# EXT_LED.net
KiCad netlist of a schematic drawn in EAGLE
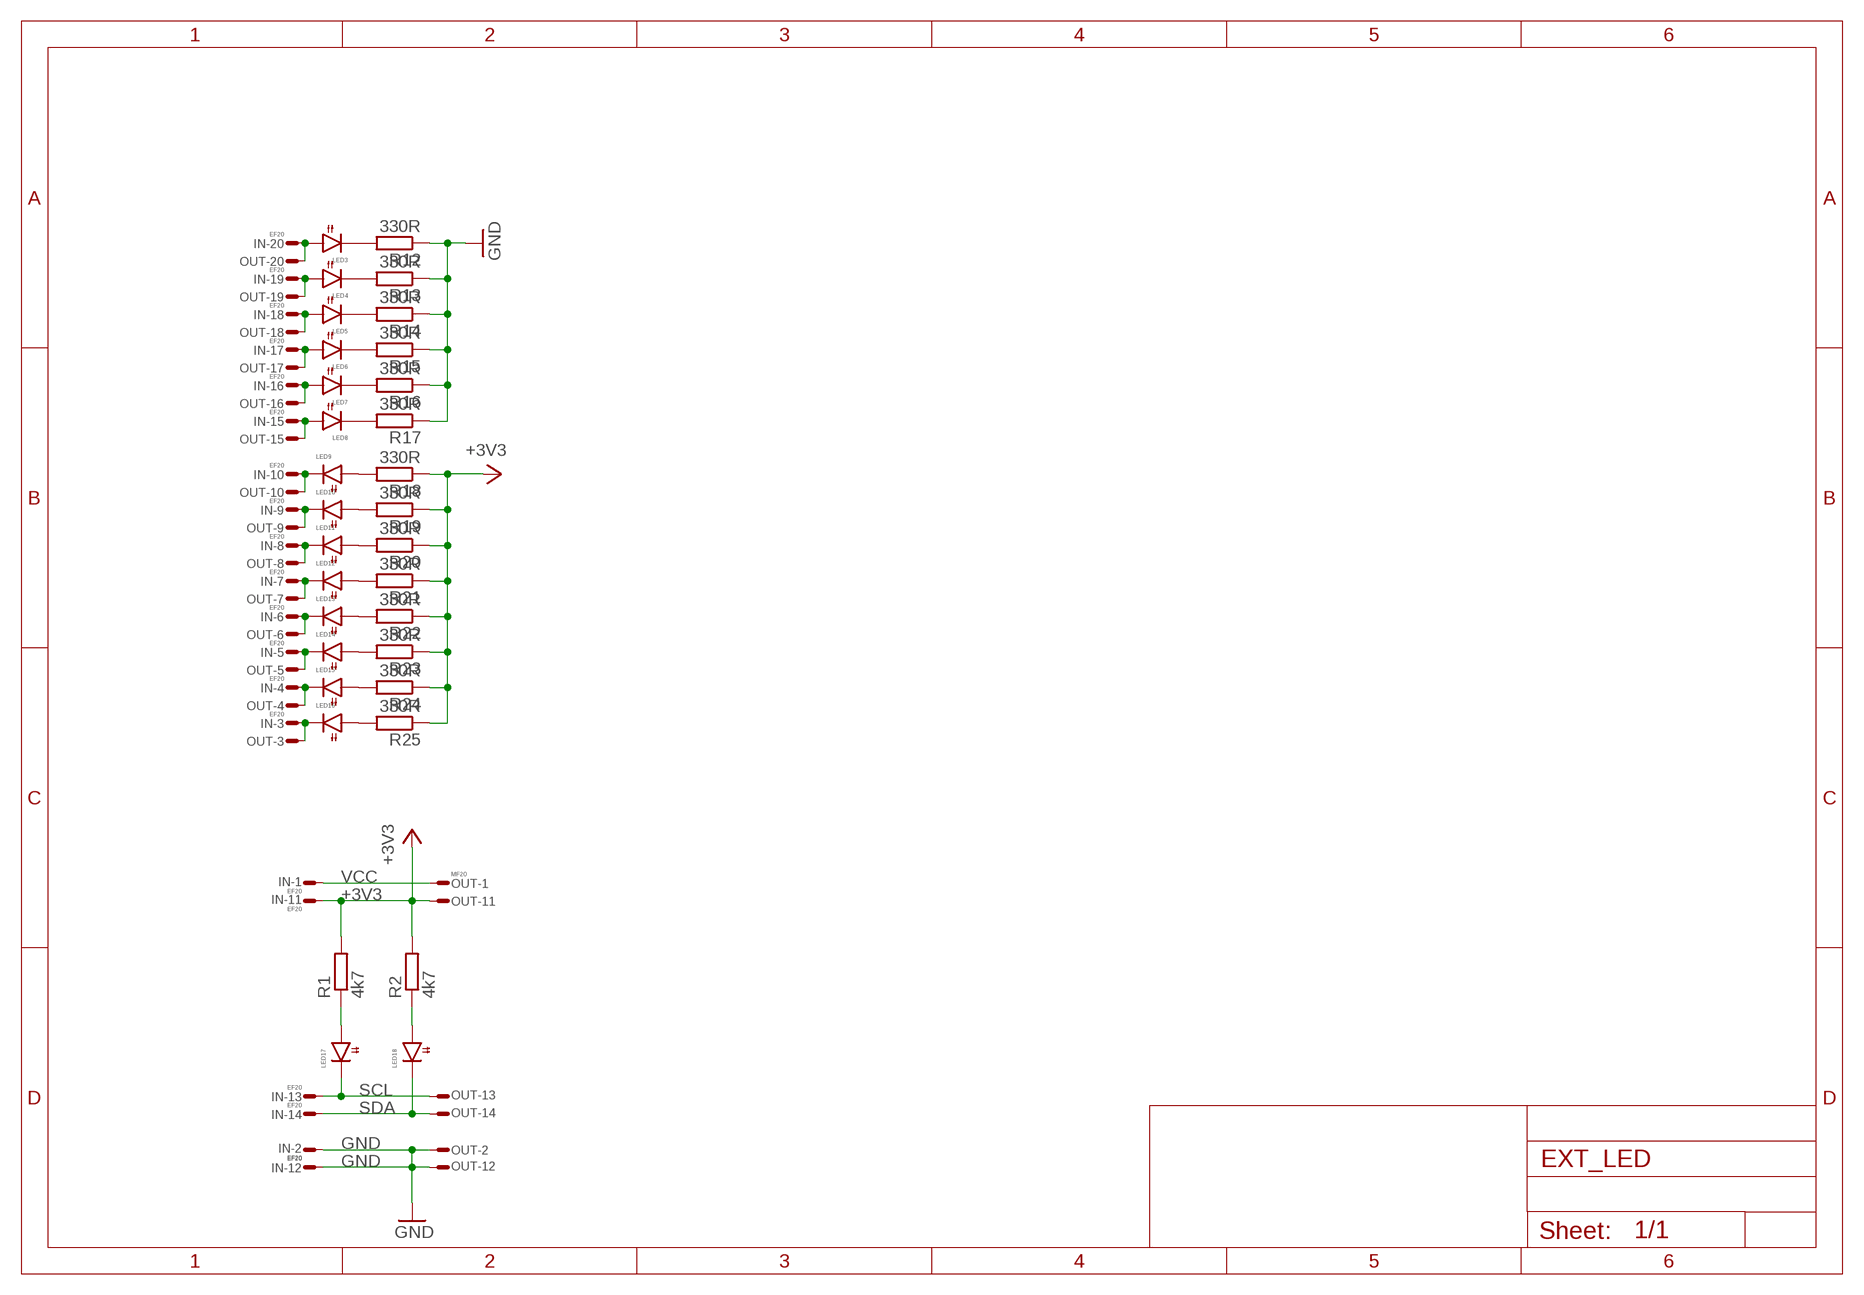
[diagram p0: schematic, sheet 1]

(export (version "E")
  (design (tool "Eeschema 10.0.6"))
  (components
    (comp (ref "IN")
      (value "EF20")
      (footprint "eagle-import:FE10-2WSS")
      (libsource (lib "eagle-import") (part "FE20ELSS"))
    )
    (comp (ref "LED3")
      (value "LED0603")
      (footprint "eagle-import:0603")
      (libsource (lib "eagle-import") (part "LED0603"))
    )
    (comp (ref "LED4")
      (value "LED0603")
      (footprint "eagle-import:0603")
      (libsource (lib "eagle-import") (part "LED0603"))
    )
    (comp (ref "LED5")
      (value "LED0603")
      (footprint "eagle-import:0603")
      (libsource (lib "eagle-import") (part "LED0603"))
    )
    (comp (ref "LED6")
      (value "LED0603")
      (footprint "eagle-import:0603")
      (libsource (lib "eagle-import") (part "LED0603"))
    )
    (comp (ref "LED7")
      (value "LED0603")
      (footprint "eagle-import:0603")
      (libsource (lib "eagle-import") (part "LED0603"))
    )
    (comp (ref "LED8")
      (value "LED0603")
      (footprint "eagle-import:0603")
      (libsource (lib "eagle-import") (part "LED0603"))
    )
    (comp (ref "LED9")
      (value "LED0603")
      (footprint "eagle-import:0603")
      (libsource (lib "eagle-import") (part "LED0603"))
    )
    (comp (ref "LED10")
      (value "LED0603")
      (footprint "eagle-import:0603")
      (libsource (lib "eagle-import") (part "LED0603"))
    )
    (comp (ref "LED11")
      (value "LED0603")
      (footprint "eagle-import:0603")
      (libsource (lib "eagle-import") (part "LED0603"))
    )
    (comp (ref "LED12")
      (value "LED0603")
      (footprint "eagle-import:0603")
      (libsource (lib "eagle-import") (part "LED0603"))
    )
    (comp (ref "LED13")
      (value "LED0603")
      (footprint "eagle-import:0603")
      (libsource (lib "eagle-import") (part "LED0603"))
    )
    (comp (ref "LED14")
      (value "LED0603")
      (footprint "eagle-import:0603")
      (libsource (lib "eagle-import") (part "LED0603"))
    )
    (comp (ref "LED15")
      (value "LED0603")
      (footprint "eagle-import:0603")
      (libsource (lib "eagle-import") (part "LED0603"))
    )
    (comp (ref "LED16")
      (value "LED0603")
      (footprint "eagle-import:0603")
      (libsource (lib "eagle-import") (part "LED0603"))
    )
    (comp (ref "LED17")
      (value "LED0603")
      (footprint "eagle-import:0603")
      (libsource (lib "eagle-import") (part "LED0603"))
    )
    (comp (ref "LED18")
      (value "LED0603")
      (footprint "eagle-import:0603")
      (libsource (lib "eagle-import") (part "LED0603"))
    )
    (comp (ref "OUT")
      (value "MF20")
      (footprint "eagle-import:ML20LS")
      (libsource (lib "eagle-import") (part "ML20?ELS"))
    )
    (comp (ref "R1")
      (value "4k7")
      (footprint "eagle-import:0603")
      (libsource (lib "eagle-import") (part "R0603"))
    )
    (comp (ref "R2")
      (value "4k7")
      (footprint "eagle-import:0603")
      (libsource (lib "eagle-import") (part "R0603"))
    )
    (comp (ref "R12")
      (value "330R")
      (footprint "eagle-import:0603")
      (libsource (lib "eagle-import") (part "R0603"))
    )
    (comp (ref "R13")
      (value "330R")
      (footprint "eagle-import:0603")
      (libsource (lib "eagle-import") (part "R0603"))
    )
    (comp (ref "R14")
      (value "330R")
      (footprint "eagle-import:0603")
      (libsource (lib "eagle-import") (part "R0603"))
    )
    (comp (ref "R15")
      (value "330R")
      (footprint "eagle-import:0603")
      (libsource (lib "eagle-import") (part "R0603"))
    )
    (comp (ref "R16")
      (value "330R")
      (footprint "eagle-import:0603")
      (libsource (lib "eagle-import") (part "R0603"))
    )
    (comp (ref "R17")
      (value "330R")
      (footprint "eagle-import:0603")
      (libsource (lib "eagle-import") (part "R0603"))
    )
    (comp (ref "R18")
      (value "330R")
      (footprint "eagle-import:0603")
      (libsource (lib "eagle-import") (part "R0603"))
    )
    (comp (ref "R19")
      (value "330R")
      (footprint "eagle-import:0603")
      (libsource (lib "eagle-import") (part "R0603"))
    )
    (comp (ref "R20")
      (value "330R")
      (footprint "eagle-import:0603")
      (libsource (lib "eagle-import") (part "R0603"))
    )
    (comp (ref "R21")
      (value "330R")
      (footprint "eagle-import:0603")
      (libsource (lib "eagle-import") (part "R0603"))
    )
    (comp (ref "R22")
      (value "330R")
      (footprint "eagle-import:0603")
      (libsource (lib "eagle-import") (part "R0603"))
    )
    (comp (ref "R23")
      (value "330R")
      (footprint "eagle-import:0603")
      (libsource (lib "eagle-import") (part "R0603"))
    )
    (comp (ref "R24")
      (value "330R")
      (footprint "eagle-import:0603")
      (libsource (lib "eagle-import") (part "R0603"))
    )
    (comp (ref "R25")
      (value "330R")
      (footprint "eagle-import:0603")
      (libsource (lib "eagle-import") (part "R0603"))
    )
  )
  (nets
    (net (code "1") (name "+3V3") (class "Default")
      (node (ref "IN") (pin "P$11") (pinfunction "S_P$11") (pintype "passive"))
      (node (ref "OUT") (pin "P$11") (pinfunction "S_P$11") (pintype "passive"))
      (node (ref "R1") (pin "2") (pinfunction "2_2") (pintype "passive"))
      (node (ref "R18") (pin "1") (pinfunction "1_1") (pintype "passive"))
      (node (ref "R19") (pin "1") (pinfunction "1_1") (pintype "passive"))
      (node (ref "R2") (pin "2") (pinfunction "2_2") (pintype "passive"))
      (node (ref "R20") (pin "1") (pinfunction "1_1") (pintype "passive"))
      (node (ref "R21") (pin "1") (pinfunction "1_1") (pintype "passive"))
      (node (ref "R22") (pin "1") (pinfunction "1_1") (pintype "passive"))
      (node (ref "R23") (pin "1") (pinfunction "1_1") (pintype "passive"))
      (node (ref "R24") (pin "1") (pinfunction "1_1") (pintype "passive"))
      (node (ref "R25") (pin "1") (pinfunction "1_1") (pintype "passive"))
    )
    (net (code "2") (name "/SCL") (class "Default")
      (node (ref "IN") (pin "P$13") (pinfunction "S_P$13") (pintype "passive"))
      (node (ref "LED17") (pin "2") (pinfunction "C_2") (pintype "bidirectional"))
      (node (ref "OUT") (pin "P$13") (pinfunction "S_P$13") (pintype "passive"))
    )
    (net (code "3") (name "/SDA") (class "Default")
      (node (ref "IN") (pin "P$14") (pinfunction "S_P$14") (pintype "passive"))
      (node (ref "LED18") (pin "2") (pinfunction "C_2") (pintype "bidirectional"))
      (node (ref "OUT") (pin "P$14") (pinfunction "S_P$14") (pintype "passive"))
    )
    (net (code "4") (name "/VCC") (class "Default")
      (node (ref "IN") (pin "P$1") (pinfunction "S_P$1") (pintype "passive"))
      (node (ref "OUT") (pin "P$1") (pinfunction "S_P$1") (pintype "passive"))
    )
    (net (code "5") (name "GND") (class "Default")
      (node (ref "IN") (pin "P$12") (pinfunction "S_P$12") (pintype "passive"))
      (node (ref "IN") (pin "P$2") (pinfunction "S_P$2") (pintype "passive"))
      (node (ref "OUT") (pin "P$12") (pinfunction "S_P$12") (pintype "passive"))
      (node (ref "OUT") (pin "P$2") (pinfunction "S_P$2") (pintype "passive"))
      (node (ref "R12") (pin "1") (pinfunction "1_1") (pintype "passive"))
      (node (ref "R13") (pin "1") (pinfunction "1_1") (pintype "passive"))
      (node (ref "R14") (pin "1") (pinfunction "1_1") (pintype "passive"))
      (node (ref "R15") (pin "1") (pinfunction "1_1") (pintype "passive"))
      (node (ref "R16") (pin "1") (pinfunction "1_1") (pintype "passive"))
      (node (ref "R17") (pin "1") (pinfunction "1_1") (pintype "passive"))
    )
    (net (code "6") (name "Net-(INB-S)") (class "Default")
      (node (ref "IN") (pin "P$10") (pinfunction "S_P$10") (pintype "passive"))
      (node (ref "LED9") (pin "2") (pinfunction "C_2") (pintype "bidirectional"))
      (node (ref "OUT") (pin "P$10") (pinfunction "S_P$10") (pintype "passive"))
    )
    (net (code "7") (name "Net-(ING-S)") (class "Default")
      (node (ref "IN") (pin "P$15") (pinfunction "S_P$15") (pintype "passive"))
      (node (ref "LED8") (pin "1") (pinfunction "A_1") (pintype "bidirectional"))
      (node (ref "OUT") (pin "P$15") (pinfunction "S_P$15") (pintype "passive"))
    )
    (net (code "8") (name "Net-(INH-S)") (class "Default")
      (node (ref "IN") (pin "P$16") (pinfunction "S_P$16") (pintype "passive"))
      (node (ref "LED7") (pin "1") (pinfunction "A_1") (pintype "bidirectional"))
      (node (ref "OUT") (pin "P$16") (pinfunction "S_P$16") (pintype "passive"))
    )
    (net (code "9") (name "Net-(INI-S)") (class "Default")
      (node (ref "IN") (pin "P$17") (pinfunction "S_P$17") (pintype "passive"))
      (node (ref "LED6") (pin "1") (pinfunction "A_1") (pintype "bidirectional"))
      (node (ref "OUT") (pin "P$17") (pinfunction "S_P$17") (pintype "passive"))
    )
    (net (code "10") (name "Net-(INJ-S)") (class "Default")
      (node (ref "IN") (pin "P$18") (pinfunction "S_P$18") (pintype "passive"))
      (node (ref "LED5") (pin "1") (pinfunction "A_1") (pintype "bidirectional"))
      (node (ref "OUT") (pin "P$18") (pinfunction "S_P$18") (pintype "passive"))
    )
    (net (code "11") (name "Net-(INK-S)") (class "Default")
      (node (ref "IN") (pin "P$19") (pinfunction "S_P$19") (pintype "passive"))
      (node (ref "LED4") (pin "1") (pinfunction "A_1") (pintype "bidirectional"))
      (node (ref "OUT") (pin "P$19") (pinfunction "S_P$19") (pintype "passive"))
    )
    (net (code "12") (name "Net-(INM-S)") (class "Default")
      (node (ref "IN") (pin "P$20") (pinfunction "S_P$20") (pintype "passive"))
      (node (ref "LED3") (pin "1") (pinfunction "A_1") (pintype "bidirectional"))
      (node (ref "OUT") (pin "P$20") (pinfunction "S_P$20") (pintype "passive"))
    )
    (net (code "13") (name "Net-(INN-S)") (class "Default")
      (node (ref "IN") (pin "P$3") (pinfunction "S_P$3") (pintype "passive"))
      (node (ref "LED16") (pin "2") (pinfunction "C_2") (pintype "bidirectional"))
      (node (ref "OUT") (pin "P$3") (pinfunction "S_P$3") (pintype "passive"))
    )
    (net (code "14") (name "Net-(INO-S)") (class "Default")
      (node (ref "IN") (pin "P$4") (pinfunction "S_P$4") (pintype "passive"))
      (node (ref "LED15") (pin "2") (pinfunction "C_2") (pintype "bidirectional"))
      (node (ref "OUT") (pin "P$4") (pinfunction "S_P$4") (pintype "passive"))
    )
    (net (code "15") (name "Net-(INP-S)") (class "Default")
      (node (ref "IN") (pin "P$5") (pinfunction "S_P$5") (pintype "passive"))
      (node (ref "LED14") (pin "2") (pinfunction "C_2") (pintype "bidirectional"))
      (node (ref "OUT") (pin "P$5") (pinfunction "S_P$5") (pintype "passive"))
    )
    (net (code "16") (name "Net-(INQ-S)") (class "Default")
      (node (ref "IN") (pin "P$6") (pinfunction "S_P$6") (pintype "passive"))
      (node (ref "LED13") (pin "2") (pinfunction "C_2") (pintype "bidirectional"))
      (node (ref "OUT") (pin "P$6") (pinfunction "S_P$6") (pintype "passive"))
    )
    (net (code "17") (name "Net-(INR-S)") (class "Default")
      (node (ref "IN") (pin "P$7") (pinfunction "S_P$7") (pintype "passive"))
      (node (ref "LED12") (pin "2") (pinfunction "C_2") (pintype "bidirectional"))
      (node (ref "OUT") (pin "P$7") (pinfunction "S_P$7") (pintype "passive"))
    )
    (net (code "18") (name "Net-(INS-S)") (class "Default")
      (node (ref "IN") (pin "P$8") (pinfunction "S_P$8") (pintype "passive"))
      (node (ref "LED11") (pin "2") (pinfunction "C_2") (pintype "bidirectional"))
      (node (ref "OUT") (pin "P$8") (pinfunction "S_P$8") (pintype "passive"))
    )
    (net (code "19") (name "Net-(INT-S)") (class "Default")
      (node (ref "IN") (pin "P$9") (pinfunction "S_P$9") (pintype "passive"))
      (node (ref "LED10") (pin "2") (pinfunction "C_2") (pintype "bidirectional"))
      (node (ref "OUT") (pin "P$9") (pinfunction "S_P$9") (pintype "passive"))
    )
    (net (code "20") (name "Net-(LED3-C)") (class "Default")
      (node (ref "LED3") (pin "2") (pinfunction "C_2") (pintype "bidirectional"))
      (node (ref "R12") (pin "2") (pinfunction "2_2") (pintype "passive"))
    )
    (net (code "21") (name "Net-(LED4-C)") (class "Default")
      (node (ref "LED4") (pin "2") (pinfunction "C_2") (pintype "bidirectional"))
      (node (ref "R13") (pin "2") (pinfunction "2_2") (pintype "passive"))
    )
    (net (code "22") (name "Net-(LED5-C)") (class "Default")
      (node (ref "LED5") (pin "2") (pinfunction "C_2") (pintype "bidirectional"))
      (node (ref "R14") (pin "2") (pinfunction "2_2") (pintype "passive"))
    )
    (net (code "23") (name "Net-(LED6-C)") (class "Default")
      (node (ref "LED6") (pin "2") (pinfunction "C_2") (pintype "bidirectional"))
      (node (ref "R15") (pin "2") (pinfunction "2_2") (pintype "passive"))
    )
    (net (code "24") (name "Net-(LED7-C)") (class "Default")
      (node (ref "LED7") (pin "2") (pinfunction "C_2") (pintype "bidirectional"))
      (node (ref "R16") (pin "2") (pinfunction "2_2") (pintype "passive"))
    )
    (net (code "25") (name "Net-(LED8-C)") (class "Default")
      (node (ref "LED8") (pin "2") (pinfunction "C_2") (pintype "bidirectional"))
      (node (ref "R17") (pin "2") (pinfunction "2_2") (pintype "passive"))
    )
    (net (code "26") (name "Net-(LED9-A)") (class "Default")
      (node (ref "LED9") (pin "1") (pinfunction "A_1") (pintype "bidirectional"))
      (node (ref "R18") (pin "2") (pinfunction "2_2") (pintype "passive"))
    )
    (net (code "27") (name "Net-(LED10-A)") (class "Default")
      (node (ref "LED10") (pin "1") (pinfunction "A_1") (pintype "bidirectional"))
      (node (ref "R19") (pin "2") (pinfunction "2_2") (pintype "passive"))
    )
    (net (code "28") (name "Net-(LED11-A)") (class "Default")
      (node (ref "LED11") (pin "1") (pinfunction "A_1") (pintype "bidirectional"))
      (node (ref "R20") (pin "2") (pinfunction "2_2") (pintype "passive"))
    )
    (net (code "29") (name "Net-(LED12-A)") (class "Default")
      (node (ref "LED12") (pin "1") (pinfunction "A_1") (pintype "bidirectional"))
      (node (ref "R21") (pin "2") (pinfunction "2_2") (pintype "passive"))
    )
    (net (code "30") (name "Net-(LED13-A)") (class "Default")
      (node (ref "LED13") (pin "1") (pinfunction "A_1") (pintype "bidirectional"))
      (node (ref "R22") (pin "2") (pinfunction "2_2") (pintype "passive"))
    )
    (net (code "31") (name "Net-(LED14-A)") (class "Default")
      (node (ref "LED14") (pin "1") (pinfunction "A_1") (pintype "bidirectional"))
      (node (ref "R23") (pin "2") (pinfunction "2_2") (pintype "passive"))
    )
    (net (code "32") (name "Net-(LED15-A)") (class "Default")
      (node (ref "LED15") (pin "1") (pinfunction "A_1") (pintype "bidirectional"))
      (node (ref "R24") (pin "2") (pinfunction "2_2") (pintype "passive"))
    )
    (net (code "33") (name "Net-(LED16-A)") (class "Default")
      (node (ref "LED16") (pin "1") (pinfunction "A_1") (pintype "bidirectional"))
      (node (ref "R25") (pin "2") (pinfunction "2_2") (pintype "passive"))
    )
    (net (code "34") (name "Net-(LED17-A)") (class "Default")
      (node (ref "LED17") (pin "1") (pinfunction "A_1") (pintype "bidirectional"))
      (node (ref "R1") (pin "1") (pinfunction "1_1") (pintype "passive"))
    )
    (net (code "35") (name "Net-(LED18-A)") (class "Default")
      (node (ref "LED18") (pin "1") (pinfunction "A_1") (pintype "bidirectional"))
      (node (ref "R2") (pin "1") (pinfunction "1_1") (pintype "passive"))
    )
  )
)
